# A400_1_BasicBackplane.net
KiCad netlist of a schematic drawn in Altium Designer
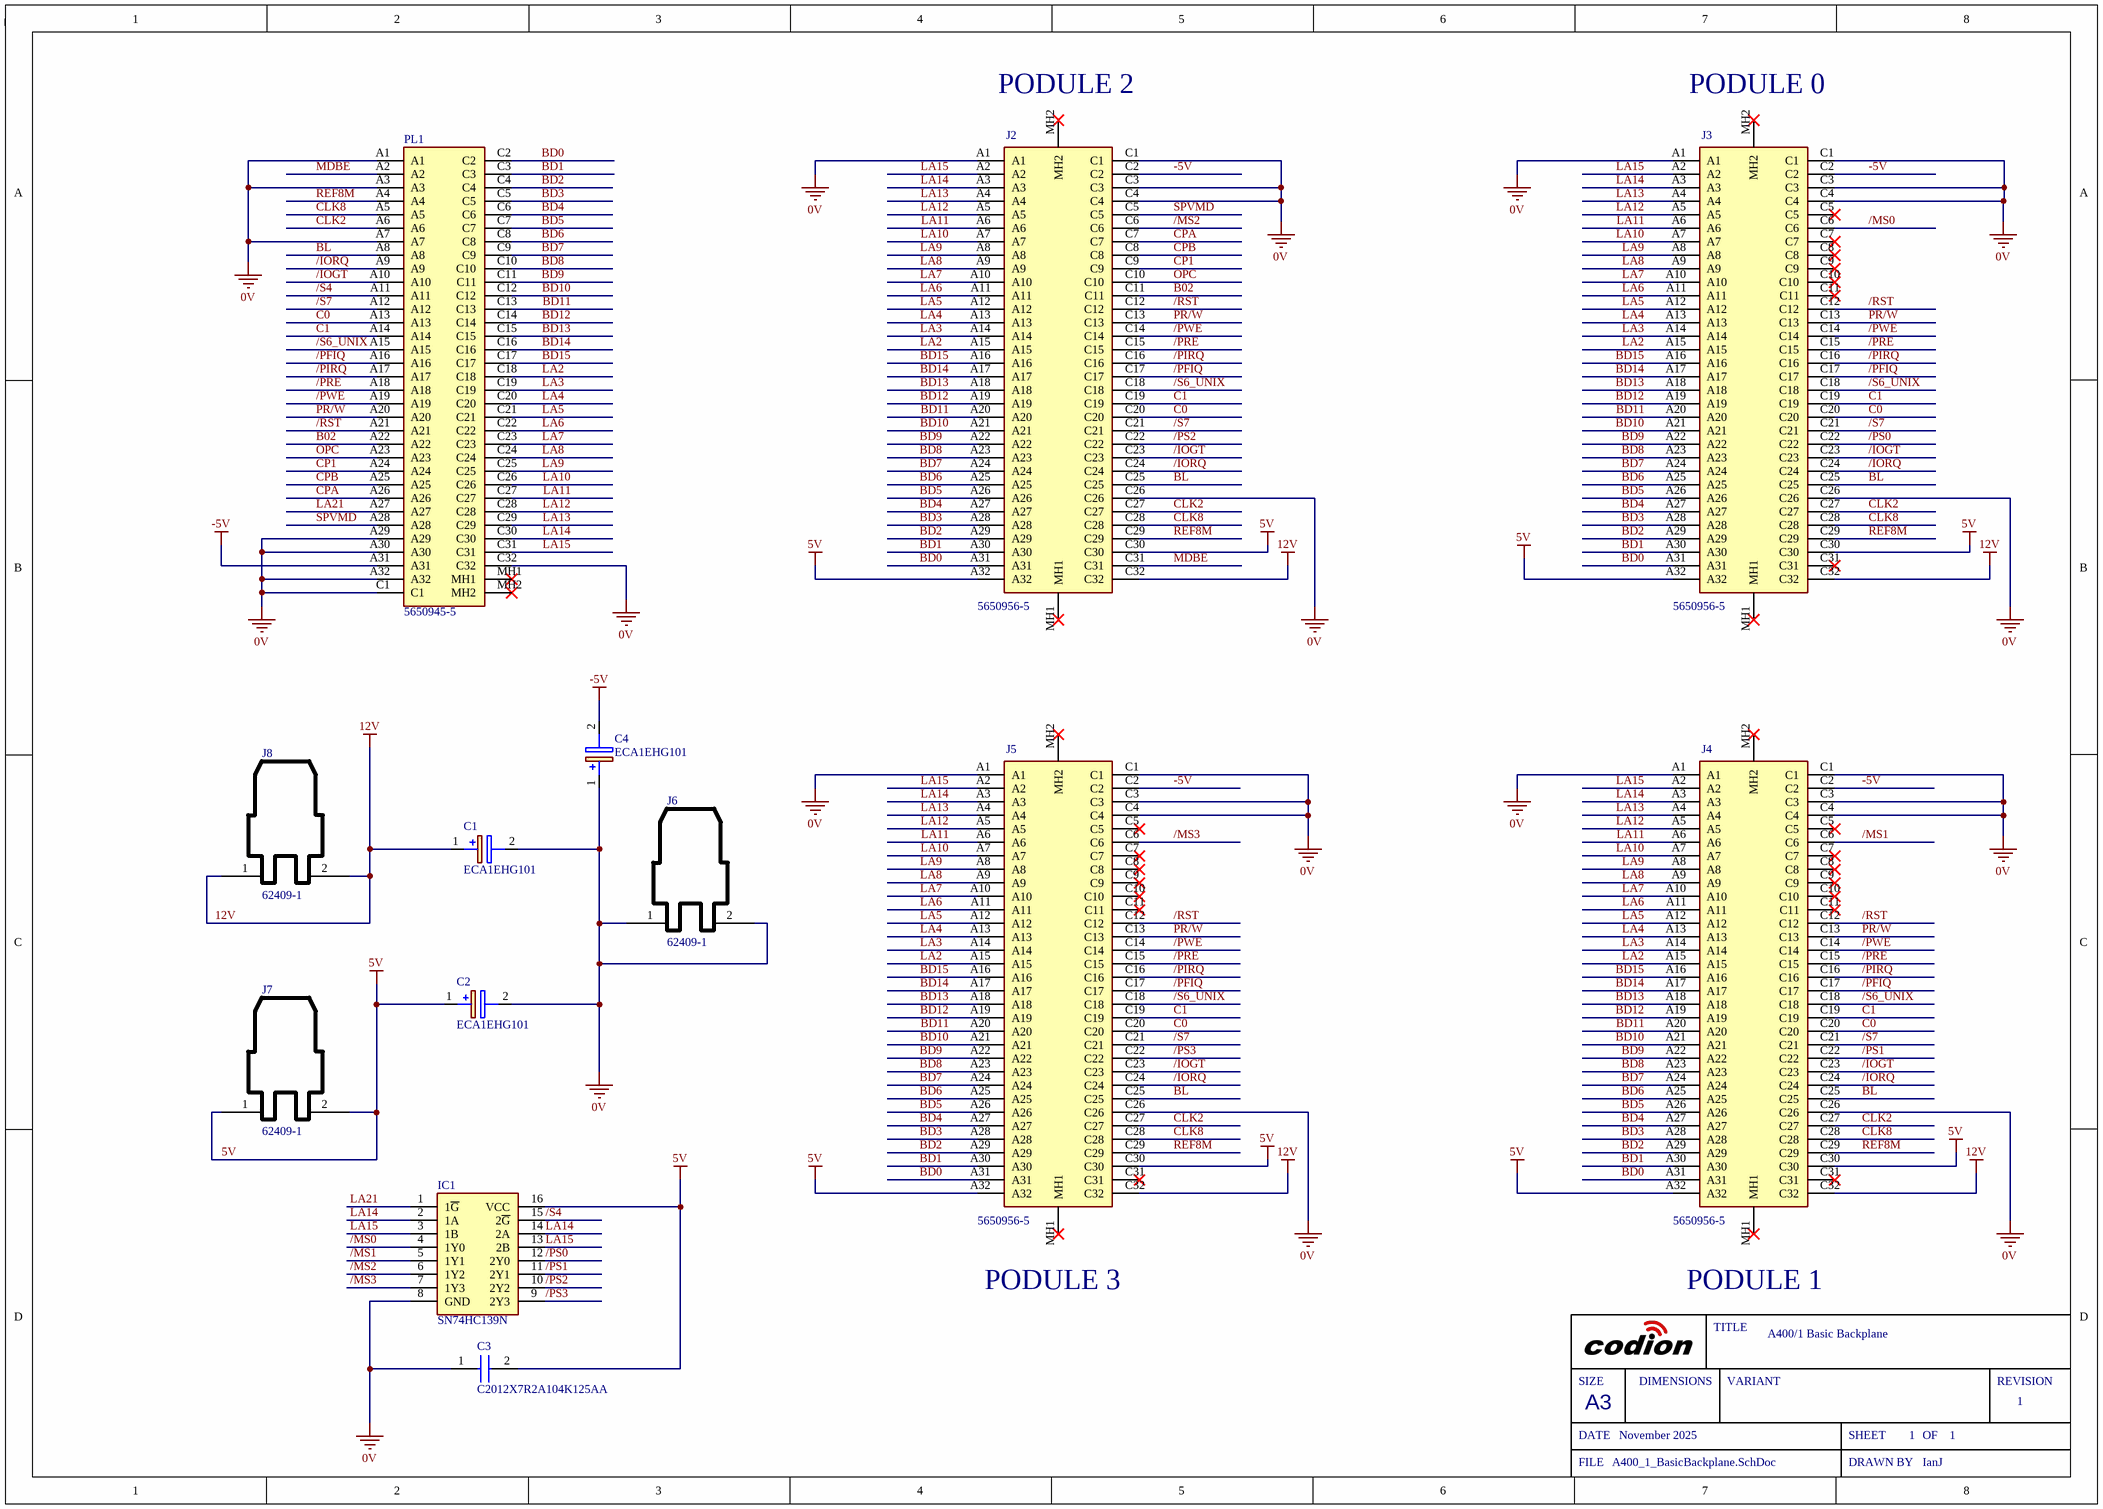
[diagram p0: A400_1_BasicBackplane.SchDoc]

(export (version "E")
  (design (tool "Eeschema 10.0.6"))
  (components
    (comp (ref "C1")
      (value "ECA1EHG101")
      (footprint "SamacSys:CAPPRD250W55D630H1220")
      (description "Capacitor Polarised")
      (libsource (lib "") (part "ECA1EHG101_1"))
    )
    (comp (ref "C2")
      (value "ECA1EHG101")
      (footprint "SamacSys:CAPPRD250W55D630H1220")
      (description "Capacitor Polarised")
      (libsource (lib "") (part "ECA1EHG101_1"))
    )
    (comp (ref "C3")
      (value "C2012X7R2A104K125AA")
      (footprint "SamacSys:CAPC2012X145N")
      (description "Capacitor")
      (fields (field (name "MOUSER PART NUMBER") "810-C2012X7R2A104K"))
      (libsource (lib "*") (part "C2012X7R2A104K125AA"))
    )
    (comp (ref "C4")
      (value "ECA1EHG101")
      (footprint "SamacSys:CAPPRD250W55D630H1220")
      (description "Capacitor Polarised")
      (libsource (lib "*") (part "ECA1EHG101"))
    )
    (comp (ref "IC1")
      (value "SN74HC139N")
      (footprint "SamacSys:DIP794W53P254L1930H508Q16N")
      (description "Integrated Circuit")
      (fields (field (name "MOUSER PART NUMBER") "595-SN74HC139N"))
      (libsource (lib "*") (part "SN74HC139N"))
    )
    (comp (ref "J2")
      (value "5650956-5")
      (footprint "SamacSys:56509565")
      (description "Connector")
      (fields (field (name "MOUSER PART NUMBER") "571-5650956-5"))
      (libsource (lib "*") (part "5650956-5"))
    )
    (comp (ref "J3")
      (value "5650956-5")
      (footprint "SamacSys:56509565")
      (description "Connector")
      (fields (field (name "MOUSER PART NUMBER") "571-5650956-5"))
      (libsource (lib "*") (part "5650956-5"))
    )
    (comp (ref "J4")
      (value "5650956-5")
      (footprint "SamacSys:56509565")
      (description "Connector")
      (fields (field (name "MOUSER PART NUMBER") "571-5650956-5"))
      (libsource (lib "*") (part "5650956-5"))
    )
    (comp (ref "J5")
      (value "5650956-5")
      (footprint "SamacSys:56509565")
      (description "Connector")
      (fields (field (name "MOUSER PART NUMBER") "571-5650956-5"))
      (libsource (lib "*") (part "5650956-5"))
    )
    (comp (ref "J6")
      (value "62409-1")
      (footprint "62409-1")
      (description "PCB Terminal, 6.35mm x 0.81mm, 0.25\" x 0.032\", Brass, 1.4 mm, Tin")
      (fields (field (name "PART NUMBER") "982-0022") (field (name "MANUFACTURER") "TE Coonectivity"))
      (libsource (lib "Local_Altium_Lib") (part "62409-1"))
    )
    (comp (ref "J7")
      (value "62409-1")
      (footprint "62409-1")
      (description "PCB Terminal, 6.35mm x 0.81mm, 0.25\" x 0.032\", Brass, 1.4 mm, Tin")
      (fields (field (name "PART NUMBER") "982-0022") (field (name "MANUFACTURER") "TE Coonectivity"))
      (libsource (lib "Local_Altium_Lib") (part "62409-1"))
    )
    (comp (ref "J8")
      (value "62409-1")
      (footprint "62409-1")
      (description "PCB Terminal, 6.35mm x 0.81mm, 0.25\" x 0.032\", Brass, 1.4 mm, Tin")
      (fields (field (name "PART NUMBER") "982-0022") (field (name "MANUFACTURER") "TE Coonectivity"))
      (libsource (lib "Local_Altium_Lib") (part "62409-1"))
    )
    (comp (ref "PL1")
      (value "5650945-5")
      (footprint "SamacSys:56509455")
      (description "Connector")
      (fields (field (name "MOUSER PART NUMBER") "571-5650945-5"))
      (libsource (lib "*") (part "5650945-5"))
    )
  )
  (nets
    (net (code "1") (name "-5V") (class "Default")
      (node (ref "C4") (pin "2") (pinfunction "-_2") (pintype "passive"))
      (node (ref "J2") (pin "C2") (pinfunction "C2_C2") (pintype "passive"))
      (node (ref "J3") (pin "C2") (pinfunction "C2_C2") (pintype "passive"))
      (node (ref "J4") (pin "C2") (pinfunction "C2_C2") (pintype "passive"))
      (node (ref "J5") (pin "C2") (pinfunction "C2_C2") (pintype "passive"))
      (node (ref "PL1") (pin "A31") (pinfunction "A31_A31") (pintype "passive"))
    )
    (net (code "2") (name "/B02") (class "Default")
      (node (ref "J2") (pin "C11") (pinfunction "C11_C11") (pintype "passive"))
      (node (ref "PL1") (pin "A22") (pinfunction "A22_A22") (pintype "passive"))
    )
    (net (code "3") (name "/BD0") (class "Default")
      (node (ref "J2") (pin "A31") (pinfunction "A31_A31") (pintype "passive"))
      (node (ref "J3") (pin "A31") (pinfunction "A31_A31") (pintype "passive"))
      (node (ref "J4") (pin "A31") (pinfunction "A31_A31") (pintype "passive"))
      (node (ref "J5") (pin "A31") (pinfunction "A31_A31") (pintype "passive"))
      (node (ref "PL1") (pin "C2") (pinfunction "C2_C2") (pintype "passive"))
    )
    (net (code "4") (name "/BD1") (class "Default")
      (node (ref "J2") (pin "A30") (pinfunction "A30_A30") (pintype "passive"))
      (node (ref "J3") (pin "A30") (pinfunction "A30_A30") (pintype "passive"))
      (node (ref "J4") (pin "A30") (pinfunction "A30_A30") (pintype "passive"))
      (node (ref "J5") (pin "A30") (pinfunction "A30_A30") (pintype "passive"))
      (node (ref "PL1") (pin "C3") (pinfunction "C3_C3") (pintype "passive"))
    )
    (net (code "5") (name "/BD2") (class "Default")
      (node (ref "J2") (pin "A29") (pinfunction "A29_A29") (pintype "passive"))
      (node (ref "J3") (pin "A29") (pinfunction "A29_A29") (pintype "passive"))
      (node (ref "J4") (pin "A29") (pinfunction "A29_A29") (pintype "passive"))
      (node (ref "J5") (pin "A29") (pinfunction "A29_A29") (pintype "passive"))
      (node (ref "PL1") (pin "C4") (pinfunction "C4_C4") (pintype "passive"))
    )
    (net (code "6") (name "/BD3") (class "Default")
      (node (ref "J2") (pin "A28") (pinfunction "A28_A28") (pintype "passive"))
      (node (ref "J3") (pin "A28") (pinfunction "A28_A28") (pintype "passive"))
      (node (ref "J4") (pin "A28") (pinfunction "A28_A28") (pintype "passive"))
      (node (ref "J5") (pin "A28") (pinfunction "A28_A28") (pintype "passive"))
      (node (ref "PL1") (pin "C5") (pinfunction "C5_C5") (pintype "passive"))
    )
    (net (code "7") (name "/BD4") (class "Default")
      (node (ref "J2") (pin "A27") (pinfunction "A27_A27") (pintype "passive"))
      (node (ref "J3") (pin "A27") (pinfunction "A27_A27") (pintype "passive"))
      (node (ref "J4") (pin "A27") (pinfunction "A27_A27") (pintype "passive"))
      (node (ref "J5") (pin "A27") (pinfunction "A27_A27") (pintype "passive"))
      (node (ref "PL1") (pin "C6") (pinfunction "C6_C6") (pintype "passive"))
    )
    (net (code "8") (name "/BD5") (class "Default")
      (node (ref "J2") (pin "A26") (pinfunction "A26_A26") (pintype "passive"))
      (node (ref "J3") (pin "A26") (pinfunction "A26_A26") (pintype "passive"))
      (node (ref "J4") (pin "A26") (pinfunction "A26_A26") (pintype "passive"))
      (node (ref "J5") (pin "A26") (pinfunction "A26_A26") (pintype "passive"))
      (node (ref "PL1") (pin "C7") (pinfunction "C7_C7") (pintype "passive"))
    )
    (net (code "9") (name "/BD6") (class "Default")
      (node (ref "J2") (pin "A25") (pinfunction "A25_A25") (pintype "passive"))
      (node (ref "J3") (pin "A25") (pinfunction "A25_A25") (pintype "passive"))
      (node (ref "J4") (pin "A25") (pinfunction "A25_A25") (pintype "passive"))
      (node (ref "J5") (pin "A25") (pinfunction "A25_A25") (pintype "passive"))
      (node (ref "PL1") (pin "C8") (pinfunction "C8_C8") (pintype "passive"))
    )
    (net (code "10") (name "/BD7") (class "Default")
      (node (ref "J2") (pin "A24") (pinfunction "A24_A24") (pintype "passive"))
      (node (ref "J3") (pin "A24") (pinfunction "A24_A24") (pintype "passive"))
      (node (ref "J4") (pin "A24") (pinfunction "A24_A24") (pintype "passive"))
      (node (ref "J5") (pin "A24") (pinfunction "A24_A24") (pintype "passive"))
      (node (ref "PL1") (pin "C9") (pinfunction "C9_C9") (pintype "passive"))
    )
    (net (code "11") (name "/BD8") (class "Default")
      (node (ref "J2") (pin "A23") (pinfunction "A23_A23") (pintype "passive"))
      (node (ref "J3") (pin "A23") (pinfunction "A23_A23") (pintype "passive"))
      (node (ref "J4") (pin "A23") (pinfunction "A23_A23") (pintype "passive"))
      (node (ref "J5") (pin "A23") (pinfunction "A23_A23") (pintype "passive"))
      (node (ref "PL1") (pin "C10") (pinfunction "C10_C10") (pintype "passive"))
    )
    (net (code "12") (name "/BD9") (class "Default")
      (node (ref "J2") (pin "A22") (pinfunction "A22_A22") (pintype "passive"))
      (node (ref "J3") (pin "A22") (pinfunction "A22_A22") (pintype "passive"))
      (node (ref "J4") (pin "A22") (pinfunction "A22_A22") (pintype "passive"))
      (node (ref "J5") (pin "A22") (pinfunction "A22_A22") (pintype "passive"))
      (node (ref "PL1") (pin "C11") (pinfunction "C11_C11") (pintype "passive"))
    )
    (net (code "13") (name "/BD10") (class "Default")
      (node (ref "J2") (pin "A21") (pinfunction "A21_A21") (pintype "passive"))
      (node (ref "J3") (pin "A21") (pinfunction "A21_A21") (pintype "passive"))
      (node (ref "J4") (pin "A21") (pinfunction "A21_A21") (pintype "passive"))
      (node (ref "J5") (pin "A21") (pinfunction "A21_A21") (pintype "passive"))
      (node (ref "PL1") (pin "C12") (pinfunction "C12_C12") (pintype "passive"))
    )
    (net (code "14") (name "/BD11") (class "Default")
      (node (ref "J2") (pin "A20") (pinfunction "A20_A20") (pintype "passive"))
      (node (ref "J3") (pin "A20") (pinfunction "A20_A20") (pintype "passive"))
      (node (ref "J4") (pin "A20") (pinfunction "A20_A20") (pintype "passive"))
      (node (ref "J5") (pin "A20") (pinfunction "A20_A20") (pintype "passive"))
      (node (ref "PL1") (pin "C13") (pinfunction "C13_C13") (pintype "passive"))
    )
    (net (code "15") (name "/BD12") (class "Default")
      (node (ref "J2") (pin "A19") (pinfunction "A19_A19") (pintype "passive"))
      (node (ref "J3") (pin "A19") (pinfunction "A19_A19") (pintype "passive"))
      (node (ref "J4") (pin "A19") (pinfunction "A19_A19") (pintype "passive"))
      (node (ref "J5") (pin "A19") (pinfunction "A19_A19") (pintype "passive"))
      (node (ref "PL1") (pin "C14") (pinfunction "C14_C14") (pintype "passive"))
    )
    (net (code "16") (name "/BD13") (class "Default")
      (node (ref "J2") (pin "A18") (pinfunction "A18_A18") (pintype "passive"))
      (node (ref "J3") (pin "A18") (pinfunction "A18_A18") (pintype "passive"))
      (node (ref "J4") (pin "A18") (pinfunction "A18_A18") (pintype "passive"))
      (node (ref "J5") (pin "A18") (pinfunction "A18_A18") (pintype "passive"))
      (node (ref "PL1") (pin "C15") (pinfunction "C15_C15") (pintype "passive"))
    )
    (net (code "17") (name "/BD14") (class "Default")
      (node (ref "J2") (pin "A17") (pinfunction "A17_A17") (pintype "passive"))
      (node (ref "J3") (pin "A17") (pinfunction "A17_A17") (pintype "passive"))
      (node (ref "J4") (pin "A17") (pinfunction "A17_A17") (pintype "passive"))
      (node (ref "J5") (pin "A17") (pinfunction "A17_A17") (pintype "passive"))
      (node (ref "PL1") (pin "C16") (pinfunction "C16_C16") (pintype "passive"))
    )
    (net (code "18") (name "/BD15") (class "Default")
      (node (ref "J2") (pin "A16") (pinfunction "A16_A16") (pintype "passive"))
      (node (ref "J3") (pin "A16") (pinfunction "A16_A16") (pintype "passive"))
      (node (ref "J4") (pin "A16") (pinfunction "A16_A16") (pintype "passive"))
      (node (ref "J5") (pin "A16") (pinfunction "A16_A16") (pintype "passive"))
      (node (ref "PL1") (pin "C17") (pinfunction "C17_C17") (pintype "passive"))
    )
    (net (code "19") (name "/BL") (class "Default")
      (node (ref "J2") (pin "C25") (pinfunction "C25_C25") (pintype "passive"))
      (node (ref "J3") (pin "C25") (pinfunction "C25_C25") (pintype "passive"))
      (node (ref "J4") (pin "C25") (pinfunction "C25_C25") (pintype "passive"))
      (node (ref "J5") (pin "C25") (pinfunction "C25_C25") (pintype "passive"))
      (node (ref "PL1") (pin "A8") (pinfunction "A8_A8") (pintype "passive"))
    )
    (net (code "20") (name "/C0") (class "Default")
      (node (ref "J2") (pin "C20") (pinfunction "C20_C20") (pintype "passive"))
      (node (ref "J3") (pin "C20") (pinfunction "C20_C20") (pintype "passive"))
      (node (ref "J4") (pin "C20") (pinfunction "C20_C20") (pintype "passive"))
      (node (ref "J5") (pin "C20") (pinfunction "C20_C20") (pintype "passive"))
      (node (ref "PL1") (pin "A13") (pinfunction "A13_A13") (pintype "passive"))
    )
    (net (code "21") (name "/C1") (class "Default")
      (node (ref "J2") (pin "C19") (pinfunction "C19_C19") (pintype "passive"))
      (node (ref "J3") (pin "C19") (pinfunction "C19_C19") (pintype "passive"))
      (node (ref "J4") (pin "C19") (pinfunction "C19_C19") (pintype "passive"))
      (node (ref "J5") (pin "C19") (pinfunction "C19_C19") (pintype "passive"))
      (node (ref "PL1") (pin "A14") (pinfunction "A14_A14") (pintype "passive"))
    )
    (net (code "22") (name "/CLK2") (class "Default")
      (node (ref "J2") (pin "C27") (pinfunction "C27_C27") (pintype "passive"))
      (node (ref "J3") (pin "C27") (pinfunction "C27_C27") (pintype "passive"))
      (node (ref "J4") (pin "C27") (pinfunction "C27_C27") (pintype "passive"))
      (node (ref "J5") (pin "C27") (pinfunction "C27_C27") (pintype "passive"))
      (node (ref "PL1") (pin "A6") (pinfunction "A6_A6") (pintype "passive"))
    )
    (net (code "23") (name "/CLK8") (class "Default")
      (node (ref "J2") (pin "C28") (pinfunction "C28_C28") (pintype "passive"))
      (node (ref "J3") (pin "C28") (pinfunction "C28_C28") (pintype "passive"))
      (node (ref "J4") (pin "C28") (pinfunction "C28_C28") (pintype "passive"))
      (node (ref "J5") (pin "C28") (pinfunction "C28_C28") (pintype "passive"))
      (node (ref "PL1") (pin "A5") (pinfunction "A5_A5") (pintype "passive"))
    )
    (net (code "24") (name "/CP1") (class "Default")
      (node (ref "J2") (pin "C9") (pinfunction "C9_C9") (pintype "passive"))
      (node (ref "PL1") (pin "A24") (pinfunction "A24_A24") (pintype "passive"))
    )
    (net (code "25") (name "/CPA") (class "Default")
      (node (ref "J2") (pin "C7") (pinfunction "C7_C7") (pintype "passive"))
      (node (ref "PL1") (pin "A26") (pinfunction "A26_A26") (pintype "passive"))
    )
    (net (code "26") (name "/CPB") (class "Default")
      (node (ref "J2") (pin "C8") (pinfunction "C8_C8") (pintype "passive"))
      (node (ref "PL1") (pin "A25") (pinfunction "A25_A25") (pintype "passive"))
    )
    (net (code "27") (name "/LA2") (class "Default")
      (node (ref "J2") (pin "A15") (pinfunction "A15_A15") (pintype "passive"))
      (node (ref "J3") (pin "A15") (pinfunction "A15_A15") (pintype "passive"))
      (node (ref "J4") (pin "A15") (pinfunction "A15_A15") (pintype "passive"))
      (node (ref "J5") (pin "A15") (pinfunction "A15_A15") (pintype "passive"))
      (node (ref "PL1") (pin "C18") (pinfunction "C18_C18") (pintype "passive"))
    )
    (net (code "28") (name "/LA3") (class "Default")
      (node (ref "J2") (pin "A14") (pinfunction "A14_A14") (pintype "passive"))
      (node (ref "J3") (pin "A14") (pinfunction "A14_A14") (pintype "passive"))
      (node (ref "J4") (pin "A14") (pinfunction "A14_A14") (pintype "passive"))
      (node (ref "J5") (pin "A14") (pinfunction "A14_A14") (pintype "passive"))
      (node (ref "PL1") (pin "C19") (pinfunction "C19_C19") (pintype "passive"))
    )
    (net (code "29") (name "/LA4") (class "Default")
      (node (ref "J2") (pin "A13") (pinfunction "A13_A13") (pintype "passive"))
      (node (ref "J3") (pin "A13") (pinfunction "A13_A13") (pintype "passive"))
      (node (ref "J4") (pin "A13") (pinfunction "A13_A13") (pintype "passive"))
      (node (ref "J5") (pin "A13") (pinfunction "A13_A13") (pintype "passive"))
      (node (ref "PL1") (pin "C20") (pinfunction "C20_C20") (pintype "passive"))
    )
    (net (code "30") (name "/LA5") (class "Default")
      (node (ref "J2") (pin "A12") (pinfunction "A12_A12") (pintype "passive"))
      (node (ref "J3") (pin "A12") (pinfunction "A12_A12") (pintype "passive"))
      (node (ref "J4") (pin "A12") (pinfunction "A12_A12") (pintype "passive"))
      (node (ref "J5") (pin "A12") (pinfunction "A12_A12") (pintype "passive"))
      (node (ref "PL1") (pin "C21") (pinfunction "C21_C21") (pintype "passive"))
    )
    (net (code "31") (name "/LA6") (class "Default")
      (node (ref "J2") (pin "A11") (pinfunction "A11_A11") (pintype "passive"))
      (node (ref "J3") (pin "A11") (pinfunction "A11_A11") (pintype "passive"))
      (node (ref "J4") (pin "A11") (pinfunction "A11_A11") (pintype "passive"))
      (node (ref "J5") (pin "A11") (pinfunction "A11_A11") (pintype "passive"))
      (node (ref "PL1") (pin "C22") (pinfunction "C22_C22") (pintype "passive"))
    )
    (net (code "32") (name "/LA7") (class "Default")
      (node (ref "J2") (pin "A10") (pinfunction "A10_A10") (pintype "passive"))
      (node (ref "J3") (pin "A10") (pinfunction "A10_A10") (pintype "passive"))
      (node (ref "J4") (pin "A10") (pinfunction "A10_A10") (pintype "passive"))
      (node (ref "J5") (pin "A10") (pinfunction "A10_A10") (pintype "passive"))
      (node (ref "PL1") (pin "C23") (pinfunction "C23_C23") (pintype "passive"))
    )
    (net (code "33") (name "/LA8") (class "Default")
      (node (ref "J2") (pin "A9") (pinfunction "A9_A9") (pintype "passive"))
      (node (ref "J3") (pin "A9") (pinfunction "A9_A9") (pintype "passive"))
      (node (ref "J4") (pin "A9") (pinfunction "A9_A9") (pintype "passive"))
      (node (ref "J5") (pin "A9") (pinfunction "A9_A9") (pintype "passive"))
      (node (ref "PL1") (pin "C24") (pinfunction "C24_C24") (pintype "passive"))
    )
    (net (code "34") (name "/LA9") (class "Default")
      (node (ref "J2") (pin "A8") (pinfunction "A8_A8") (pintype "passive"))
      (node (ref "J3") (pin "A8") (pinfunction "A8_A8") (pintype "passive"))
      (node (ref "J4") (pin "A8") (pinfunction "A8_A8") (pintype "passive"))
      (node (ref "J5") (pin "A8") (pinfunction "A8_A8") (pintype "passive"))
      (node (ref "PL1") (pin "C25") (pinfunction "C25_C25") (pintype "passive"))
    )
    (net (code "35") (name "/LA10") (class "Default")
      (node (ref "J2") (pin "A7") (pinfunction "A7_A7") (pintype "passive"))
      (node (ref "J3") (pin "A7") (pinfunction "A7_A7") (pintype "passive"))
      (node (ref "J4") (pin "A7") (pinfunction "A7_A7") (pintype "passive"))
      (node (ref "J5") (pin "A7") (pinfunction "A7_A7") (pintype "passive"))
      (node (ref "PL1") (pin "C26") (pinfunction "C26_C26") (pintype "passive"))
    )
    (net (code "36") (name "/LA11") (class "Default")
      (node (ref "J2") (pin "A6") (pinfunction "A6_A6") (pintype "passive"))
      (node (ref "J3") (pin "A6") (pinfunction "A6_A6") (pintype "passive"))
      (node (ref "J4") (pin "A6") (pinfunction "A6_A6") (pintype "passive"))
      (node (ref "J5") (pin "A6") (pinfunction "A6_A6") (pintype "passive"))
      (node (ref "PL1") (pin "C27") (pinfunction "C27_C27") (pintype "passive"))
    )
    (net (code "37") (name "/LA12") (class "Default")
      (node (ref "J2") (pin "A5") (pinfunction "A5_A5") (pintype "passive"))
      (node (ref "J3") (pin "A5") (pinfunction "A5_A5") (pintype "passive"))
      (node (ref "J4") (pin "A5") (pinfunction "A5_A5") (pintype "passive"))
      (node (ref "J5") (pin "A5") (pinfunction "A5_A5") (pintype "passive"))
      (node (ref "PL1") (pin "C28") (pinfunction "C28_C28") (pintype "passive"))
    )
    (net (code "38") (name "/LA13") (class "Default")
      (node (ref "J2") (pin "A4") (pinfunction "A4_A4") (pintype "passive"))
      (node (ref "J3") (pin "A4") (pinfunction "A4_A4") (pintype "passive"))
      (node (ref "J4") (pin "A4") (pinfunction "A4_A4") (pintype "passive"))
      (node (ref "J5") (pin "A4") (pinfunction "A4_A4") (pintype "passive"))
      (node (ref "PL1") (pin "C29") (pinfunction "C29_C29") (pintype "passive"))
    )
    (net (code "39") (name "/LA14") (class "Default")
      (node (ref "IC1") (pin "14") (pinfunction "2A_14") (pintype "passive"))
      (node (ref "IC1") (pin "2") (pinfunction "1A_2") (pintype "passive"))
      (node (ref "J2") (pin "A3") (pinfunction "A3_A3") (pintype "passive"))
      (node (ref "J3") (pin "A3") (pinfunction "A3_A3") (pintype "passive"))
      (node (ref "J4") (pin "A3") (pinfunction "A3_A3") (pintype "passive"))
      (node (ref "J5") (pin "A3") (pinfunction "A3_A3") (pintype "passive"))
      (node (ref "PL1") (pin "C30") (pinfunction "C30_C30") (pintype "passive"))
    )
    (net (code "40") (name "/LA15") (class "Default")
      (node (ref "IC1") (pin "13") (pinfunction "2B_13") (pintype "passive"))
      (node (ref "IC1") (pin "3") (pinfunction "1B_3") (pintype "passive"))
      (node (ref "J2") (pin "A2") (pinfunction "A2_A2") (pintype "passive"))
      (node (ref "J3") (pin "A2") (pinfunction "A2_A2") (pintype "passive"))
      (node (ref "J4") (pin "A2") (pinfunction "A2_A2") (pintype "passive"))
      (node (ref "J5") (pin "A2") (pinfunction "A2_A2") (pintype "passive"))
      (node (ref "PL1") (pin "C31") (pinfunction "C31_C31") (pintype "passive"))
    )
    (net (code "41") (name "/LA21") (class "Default")
      (node (ref "IC1") (pin "1") (pinfunction "1~{G}_1") (pintype "passive"))
      (node (ref "PL1") (pin "A27") (pinfunction "A27_A27") (pintype "passive"))
    )
    (net (code "42") (name "/MDBE") (class "Default")
      (node (ref "J2") (pin "C31") (pinfunction "C31_C31") (pintype "passive"))
      (node (ref "PL1") (pin "A2") (pinfunction "A2_A2") (pintype "passive"))
    )
    (net (code "43") (name "/OPC") (class "Default")
      (node (ref "J2") (pin "C10") (pinfunction "C10_C10") (pintype "passive"))
      (node (ref "PL1") (pin "A23") (pinfunction "A23_A23") (pintype "passive"))
    )
    (net (code "44") (name "/PR{slash}W") (class "Default")
      (node (ref "J2") (pin "C13") (pinfunction "C13_C13") (pintype "passive"))
      (node (ref "J3") (pin "C13") (pinfunction "C13_C13") (pintype "passive"))
      (node (ref "J4") (pin "C13") (pinfunction "C13_C13") (pintype "passive"))
      (node (ref "J5") (pin "C13") (pinfunction "C13_C13") (pintype "passive"))
      (node (ref "PL1") (pin "A20") (pinfunction "A20_A20") (pintype "passive"))
    )
    (net (code "45") (name "/REF8M") (class "Default")
      (node (ref "J2") (pin "C29") (pinfunction "C29_C29") (pintype "passive"))
      (node (ref "J3") (pin "C29") (pinfunction "C29_C29") (pintype "passive"))
      (node (ref "J4") (pin "C29") (pinfunction "C29_C29") (pintype "passive"))
      (node (ref "J5") (pin "C29") (pinfunction "C29_C29") (pintype "passive"))
      (node (ref "PL1") (pin "A4") (pinfunction "A4_A4") (pintype "passive"))
    )
    (net (code "46") (name "/SPVMD") (class "Default")
      (node (ref "J2") (pin "C5") (pinfunction "C5_C5") (pintype "passive"))
      (node (ref "PL1") (pin "A28") (pinfunction "A28_A28") (pintype "passive"))
    )
    (net (code "47") (name "/{slash}IOGT") (class "Default")
      (node (ref "J2") (pin "C23") (pinfunction "C23_C23") (pintype "passive"))
      (node (ref "J3") (pin "C23") (pinfunction "C23_C23") (pintype "passive"))
      (node (ref "J4") (pin "C23") (pinfunction "C23_C23") (pintype "passive"))
      (node (ref "J5") (pin "C23") (pinfunction "C23_C23") (pintype "passive"))
      (node (ref "PL1") (pin "A10") (pinfunction "A10_A10") (pintype "passive"))
    )
    (net (code "48") (name "/{slash}IORQ") (class "Default")
      (node (ref "J2") (pin "C24") (pinfunction "C24_C24") (pintype "passive"))
      (node (ref "J3") (pin "C24") (pinfunction "C24_C24") (pintype "passive"))
      (node (ref "J4") (pin "C24") (pinfunction "C24_C24") (pintype "passive"))
      (node (ref "J5") (pin "C24") (pinfunction "C24_C24") (pintype "passive"))
      (node (ref "PL1") (pin "A9") (pinfunction "A9_A9") (pintype "passive"))
    )
    (net (code "49") (name "/{slash}MS0") (class "Default")
      (node (ref "IC1") (pin "4") (pinfunction "1Y0_4") (pintype "passive"))
      (node (ref "J3") (pin "C6") (pinfunction "C6_C6") (pintype "passive"))
    )
    (net (code "50") (name "/{slash}MS1") (class "Default")
      (node (ref "IC1") (pin "5") (pinfunction "1Y1_5") (pintype "passive"))
      (node (ref "J4") (pin "C6") (pinfunction "C6_C6") (pintype "passive"))
    )
    (net (code "51") (name "/{slash}MS2") (class "Default")
      (node (ref "IC1") (pin "6") (pinfunction "1Y2_6") (pintype "passive"))
      (node (ref "J2") (pin "C6") (pinfunction "C6_C6") (pintype "passive"))
    )
    (net (code "52") (name "/{slash}MS3") (class "Default")
      (node (ref "IC1") (pin "7") (pinfunction "1Y3_7") (pintype "passive"))
      (node (ref "J5") (pin "C6") (pinfunction "C6_C6") (pintype "passive"))
    )
    (net (code "53") (name "/{slash}PFIQ") (class "Default")
      (node (ref "J2") (pin "C17") (pinfunction "C17_C17") (pintype "passive"))
      (node (ref "J3") (pin "C17") (pinfunction "C17_C17") (pintype "passive"))
      (node (ref "J4") (pin "C17") (pinfunction "C17_C17") (pintype "passive"))
      (node (ref "J5") (pin "C17") (pinfunction "C17_C17") (pintype "passive"))
      (node (ref "PL1") (pin "A16") (pinfunction "A16_A16") (pintype "passive"))
    )
    (net (code "54") (name "/{slash}PIRQ") (class "Default")
      (node (ref "J2") (pin "C16") (pinfunction "C16_C16") (pintype "passive"))
      (node (ref "J3") (pin "C16") (pinfunction "C16_C16") (pintype "passive"))
      (node (ref "J4") (pin "C16") (pinfunction "C16_C16") (pintype "passive"))
      (node (ref "J5") (pin "C16") (pinfunction "C16_C16") (pintype "passive"))
      (node (ref "PL1") (pin "A17") (pinfunction "A17_A17") (pintype "passive"))
    )
    (net (code "55") (name "/{slash}PRE") (class "Default")
      (node (ref "J2") (pin "C15") (pinfunction "C15_C15") (pintype "passive"))
      (node (ref "J3") (pin "C15") (pinfunction "C15_C15") (pintype "passive"))
      (node (ref "J4") (pin "C15") (pinfunction "C15_C15") (pintype "passive"))
      (node (ref "J5") (pin "C15") (pinfunction "C15_C15") (pintype "passive"))
      (node (ref "PL1") (pin "A18") (pinfunction "A18_A18") (pintype "passive"))
    )
    (net (code "56") (name "/{slash}PS0") (class "Default")
      (node (ref "IC1") (pin "12") (pinfunction "2Y0_12") (pintype "passive"))
      (node (ref "J3") (pin "C22") (pinfunction "C22_C22") (pintype "passive"))
    )
    (net (code "57") (name "/{slash}PS1") (class "Default")
      (node (ref "IC1") (pin "11") (pinfunction "2Y1_11") (pintype "passive"))
      (node (ref "J4") (pin "C22") (pinfunction "C22_C22") (pintype "passive"))
    )
    (net (code "58") (name "/{slash}PS2") (class "Default")
      (node (ref "IC1") (pin "10") (pinfunction "2Y2_10") (pintype "passive"))
      (node (ref "J2") (pin "C22") (pinfunction "C22_C22") (pintype "passive"))
    )
    (net (code "59") (name "/{slash}PS3") (class "Default")
      (node (ref "IC1") (pin "9") (pinfunction "2Y3_9") (pintype "passive"))
      (node (ref "J5") (pin "C22") (pinfunction "C22_C22") (pintype "passive"))
    )
    (net (code "60") (name "/{slash}PWE") (class "Default")
      (node (ref "J2") (pin "C14") (pinfunction "C14_C14") (pintype "passive"))
      (node (ref "J3") (pin "C14") (pinfunction "C14_C14") (pintype "passive"))
      (node (ref "J4") (pin "C14") (pinfunction "C14_C14") (pintype "passive"))
      (node (ref "J5") (pin "C14") (pinfunction "C14_C14") (pintype "passive"))
      (node (ref "PL1") (pin "A19") (pinfunction "A19_A19") (pintype "passive"))
    )
    (net (code "61") (name "/{slash}RST") (class "Default")
      (node (ref "J2") (pin "C12") (pinfunction "C12_C12") (pintype "passive"))
      (node (ref "J3") (pin "C12") (pinfunction "C12_C12") (pintype "passive"))
      (node (ref "J4") (pin "C12") (pinfunction "C12_C12") (pintype "passive"))
      (node (ref "J5") (pin "C12") (pinfunction "C12_C12") (pintype "passive"))
      (node (ref "PL1") (pin "A21") (pinfunction "A21_A21") (pintype "passive"))
    )
    (net (code "62") (name "/{slash}S4") (class "Default")
      (node (ref "IC1") (pin "15") (pinfunction "2~{G}_15") (pintype "passive"))
      (node (ref "PL1") (pin "A11") (pinfunction "A11_A11") (pintype "passive"))
    )
    (net (code "63") (name "/{slash}S6_UNIX") (class "Default")
      (node (ref "J2") (pin "C18") (pinfunction "C18_C18") (pintype "passive"))
      (node (ref "J3") (pin "C18") (pinfunction "C18_C18") (pintype "passive"))
      (node (ref "J4") (pin "C18") (pinfunction "C18_C18") (pintype "passive"))
      (node (ref "J5") (pin "C18") (pinfunction "C18_C18") (pintype "passive"))
      (node (ref "PL1") (pin "A15") (pinfunction "A15_A15") (pintype "passive"))
    )
    (net (code "64") (name "/{slash}S7") (class "Default")
      (node (ref "J2") (pin "C21") (pinfunction "C21_C21") (pintype "passive"))
      (node (ref "J3") (pin "C21") (pinfunction "C21_C21") (pintype "passive"))
      (node (ref "J4") (pin "C21") (pinfunction "C21_C21") (pintype "passive"))
      (node (ref "J5") (pin "C21") (pinfunction "C21_C21") (pintype "passive"))
      (node (ref "PL1") (pin "A12") (pinfunction "A12_A12") (pintype "passive"))
    )
    (net (code "65") (name "0V") (class "Default")
      (node (ref "C1") (pin "2") (pinfunction "-_2") (pintype "passive"))
      (node (ref "C2") (pin "2") (pinfunction "-_2") (pintype "passive"))
      (node (ref "C3") (pin "1") (pinfunction "1_1") (pintype "passive"))
      (node (ref "C4") (pin "1") (pinfunction "+_1") (pintype "passive"))
      (node (ref "IC1") (pin "8") (pinfunction "GND_8") (pintype "passive"))
      (node (ref "J2") (pin "A1") (pinfunction "A1_A1") (pintype "passive"))
      (node (ref "J2") (pin "C1") (pinfunction "C1_C1") (pintype "passive"))
      (node (ref "J2") (pin "C26") (pinfunction "C26_C26") (pintype "passive"))
      (node (ref "J2") (pin "C3") (pinfunction "C3_C3") (pintype "passive"))
      (node (ref "J2") (pin "C4") (pinfunction "C4_C4") (pintype "passive"))
      (node (ref "J3") (pin "A1") (pinfunction "A1_A1") (pintype "passive"))
      (node (ref "J3") (pin "C1") (pinfunction "C1_C1") (pintype "passive"))
      (node (ref "J3") (pin "C26") (pinfunction "C26_C26") (pintype "passive"))
      (node (ref "J3") (pin "C3") (pinfunction "C3_C3") (pintype "passive"))
      (node (ref "J3") (pin "C4") (pinfunction "C4_C4") (pintype "passive"))
      (node (ref "J4") (pin "A1") (pinfunction "A1_A1") (pintype "passive"))
      (node (ref "J4") (pin "C1") (pinfunction "C1_C1") (pintype "passive"))
      (node (ref "J4") (pin "C26") (pinfunction "C26_C26") (pintype "passive"))
      (node (ref "J4") (pin "C3") (pinfunction "C3_C3") (pintype "passive"))
      (node (ref "J4") (pin "C4") (pinfunction "C4_C4") (pintype "passive"))
      (node (ref "J5") (pin "A1") (pinfunction "A1_A1") (pintype "passive"))
      (node (ref "J5") (pin "C1") (pinfunction "C1_C1") (pintype "passive"))
      (node (ref "J5") (pin "C26") (pinfunction "C26_C26") (pintype "passive"))
      (node (ref "J5") (pin "C3") (pinfunction "C3_C3") (pintype "passive"))
      (node (ref "J5") (pin "C4") (pinfunction "C4_C4") (pintype "passive"))
      (node (ref "J6") (pin "1") (pintype "power_in"))
      (node (ref "J6") (pin "2") (pintype "power_in"))
      (node (ref "PL1") (pin "A1") (pinfunction "A1_A1") (pintype "passive"))
      (node (ref "PL1") (pin "A29") (pinfunction "A29_A29") (pintype "passive"))
      (node (ref "PL1") (pin "A3") (pinfunction "A3_A3") (pintype "passive"))
      (node (ref "PL1") (pin "A30") (pinfunction "A30_A30") (pintype "passive"))
      (node (ref "PL1") (pin "A32") (pinfunction "A32_A32") (pintype "passive"))
      (node (ref "PL1") (pin "A7") (pinfunction "A7_A7") (pintype "passive"))
      (node (ref "PL1") (pin "C1") (pinfunction "C1_C1") (pintype "passive"))
      (node (ref "PL1") (pin "C32") (pinfunction "C32_C32") (pintype "passive"))
    )
    (net (code "66") (name "5V") (class "Default")
      (node (ref "C2") (pin "1") (pinfunction "+_1") (pintype "passive"))
      (node (ref "C3") (pin "2") (pinfunction "2_2") (pintype "passive"))
      (node (ref "IC1") (pin "16") (pinfunction "VCC_16") (pintype "passive"))
      (node (ref "J2") (pin "A32") (pinfunction "A32_A32") (pintype "passive"))
      (node (ref "J2") (pin "C30") (pinfunction "C30_C30") (pintype "passive"))
      (node (ref "J3") (pin "A32") (pinfunction "A32_A32") (pintype "passive"))
      (node (ref "J3") (pin "C30") (pinfunction "C30_C30") (pintype "passive"))
      (node (ref "J4") (pin "A32") (pinfunction "A32_A32") (pintype "passive"))
      (node (ref "J4") (pin "C30") (pinfunction "C30_C30") (pintype "passive"))
      (node (ref "J5") (pin "A32") (pinfunction "A32_A32") (pintype "passive"))
      (node (ref "J5") (pin "C30") (pinfunction "C30_C30") (pintype "passive"))
      (node (ref "J7") (pin "1") (pintype "power_in"))
      (node (ref "J7") (pin "2") (pintype "power_in"))
    )
    (net (code "67") (name "12V") (class "Default")
      (node (ref "C1") (pin "1") (pinfunction "+_1") (pintype "passive"))
      (node (ref "J2") (pin "C32") (pinfunction "C32_C32") (pintype "passive"))
      (node (ref "J3") (pin "C32") (pinfunction "C32_C32") (pintype "passive"))
      (node (ref "J4") (pin "C32") (pinfunction "C32_C32") (pintype "passive"))
      (node (ref "J5") (pin "C32") (pinfunction "C32_C32") (pintype "passive"))
      (node (ref "J8") (pin "1") (pintype "power_in"))
      (node (ref "J8") (pin "2") (pintype "power_in"))
    )
    (net (code "68") (name "unconnected-(J2-PadMH1)") (class "Default")
      (node (ref "J2") (pin "MH1") (pinfunction "MH1_MH1") (pintype "passive+no_connect"))
    )
    (net (code "69") (name "unconnected-(J2-PadMH2)") (class "Default")
      (node (ref "J2") (pin "MH2") (pinfunction "MH2_MH2") (pintype "passive+no_connect"))
    )
    (net (code "70") (name "unconnected-(J3-PadC5)") (class "Default")
      (node (ref "J3") (pin "C5") (pinfunction "C5_C5") (pintype "passive+no_connect"))
    )
    (net (code "71") (name "unconnected-(J3-PadC7)") (class "Default")
      (node (ref "J3") (pin "C7") (pinfunction "C7_C7") (pintype "passive+no_connect"))
    )
    (net (code "72") (name "unconnected-(J3-PadC8)") (class "Default")
      (node (ref "J3") (pin "C8") (pinfunction "C8_C8") (pintype "passive+no_connect"))
    )
    (net (code "73") (name "unconnected-(J3-PadC9)") (class "Default")
      (node (ref "J3") (pin "C9") (pinfunction "C9_C9") (pintype "passive+no_connect"))
    )
    (net (code "74") (name "unconnected-(J3-PadC10)") (class "Default")
      (node (ref "J3") (pin "C10") (pinfunction "C10_C10") (pintype "passive+no_connect"))
    )
    (net (code "75") (name "unconnected-(J3-PadC11)") (class "Default")
      (node (ref "J3") (pin "C11") (pinfunction "C11_C11") (pintype "passive+no_connect"))
    )
    (net (code "76") (name "unconnected-(J3-PadC31)") (class "Default")
      (node (ref "J3") (pin "C31") (pinfunction "C31_C31") (pintype "passive+no_connect"))
    )
    (net (code "77") (name "unconnected-(J3-PadMH1)") (class "Default")
      (node (ref "J3") (pin "MH1") (pinfunction "MH1_MH1") (pintype "passive+no_connect"))
    )
    (net (code "78") (name "unconnected-(J3-PadMH2)") (class "Default")
      (node (ref "J3") (pin "MH2") (pinfunction "MH2_MH2") (pintype "passive+no_connect"))
    )
    (net (code "79") (name "unconnected-(J4-PadC5)") (class "Default")
      (node (ref "J4") (pin "C5") (pinfunction "C5_C5") (pintype "passive+no_connect"))
    )
    (net (code "80") (name "unconnected-(J4-PadC7)") (class "Default")
      (node (ref "J4") (pin "C7") (pinfunction "C7_C7") (pintype "passive+no_connect"))
    )
    (net (code "81") (name "unconnected-(J4-PadC8)") (class "Default")
      (node (ref "J4") (pin "C8") (pinfunction "C8_C8") (pintype "passive+no_connect"))
    )
    (net (code "82") (name "unconnected-(J4-PadC9)") (class "Default")
      (node (ref "J4") (pin "C9") (pinfunction "C9_C9") (pintype "passive+no_connect"))
    )
    (net (code "83") (name "unconnected-(J4-PadC10)") (class "Default")
      (node (ref "J4") (pin "C10") (pinfunction "C10_C10") (pintype "passive+no_connect"))
    )
    (net (code "84") (name "unconnected-(J4-PadC11)") (class "Default")
      (node (ref "J4") (pin "C11") (pinfunction "C11_C11") (pintype "passive+no_connect"))
    )
    (net (code "85") (name "unconnected-(J4-PadC31)") (class "Default")
      (node (ref "J4") (pin "C31") (pinfunction "C31_C31") (pintype "passive+no_connect"))
    )
    (net (code "86") (name "unconnected-(J4-PadMH1)") (class "Default")
      (node (ref "J4") (pin "MH1") (pinfunction "MH1_MH1") (pintype "passive+no_connect"))
    )
    (net (code "87") (name "unconnected-(J4-PadMH2)") (class "Default")
      (node (ref "J4") (pin "MH2") (pinfunction "MH2_MH2") (pintype "passive+no_connect"))
    )
    (net (code "88") (name "unconnected-(J5-PadC5)") (class "Default")
      (node (ref "J5") (pin "C5") (pinfunction "C5_C5") (pintype "passive+no_connect"))
    )
    (net (code "89") (name "unconnected-(J5-PadC7)") (class "Default")
      (node (ref "J5") (pin "C7") (pinfunction "C7_C7") (pintype "passive+no_connect"))
    )
    (net (code "90") (name "unconnected-(J5-PadC8)") (class "Default")
      (node (ref "J5") (pin "C8") (pinfunction "C8_C8") (pintype "passive+no_connect"))
    )
    (net (code "91") (name "unconnected-(J5-PadC9)") (class "Default")
      (node (ref "J5") (pin "C9") (pinfunction "C9_C9") (pintype "passive+no_connect"))
    )
    (net (code "92") (name "unconnected-(J5-PadC10)") (class "Default")
      (node (ref "J5") (pin "C10") (pinfunction "C10_C10") (pintype "passive+no_connect"))
    )
    (net (code "93") (name "unconnected-(J5-PadC11)") (class "Default")
      (node (ref "J5") (pin "C11") (pinfunction "C11_C11") (pintype "passive+no_connect"))
    )
    (net (code "94") (name "unconnected-(J5-PadC31)") (class "Default")
      (node (ref "J5") (pin "C31") (pinfunction "C31_C31") (pintype "passive+no_connect"))
    )
    (net (code "95") (name "unconnected-(J5-PadMH1)") (class "Default")
      (node (ref "J5") (pin "MH1") (pinfunction "MH1_MH1") (pintype "passive+no_connect"))
    )
    (net (code "96") (name "unconnected-(J5-PadMH2)") (class "Default")
      (node (ref "J5") (pin "MH2") (pinfunction "MH2_MH2") (pintype "passive+no_connect"))
    )
    (net (code "97") (name "unconnected-(PL1-PadMH1)") (class "Default")
      (node (ref "PL1") (pin "MH1") (pinfunction "MH1_MH1") (pintype "passive+no_connect"))
    )
    (net (code "98") (name "unconnected-(PL1-PadMH2)") (class "Default")
      (node (ref "PL1") (pin "MH2") (pinfunction "MH2_MH2") (pintype "passive+no_connect"))
    )
  )
)
